# eprom-player.net
KiCad netlist of a schematic drawn in EAGLE
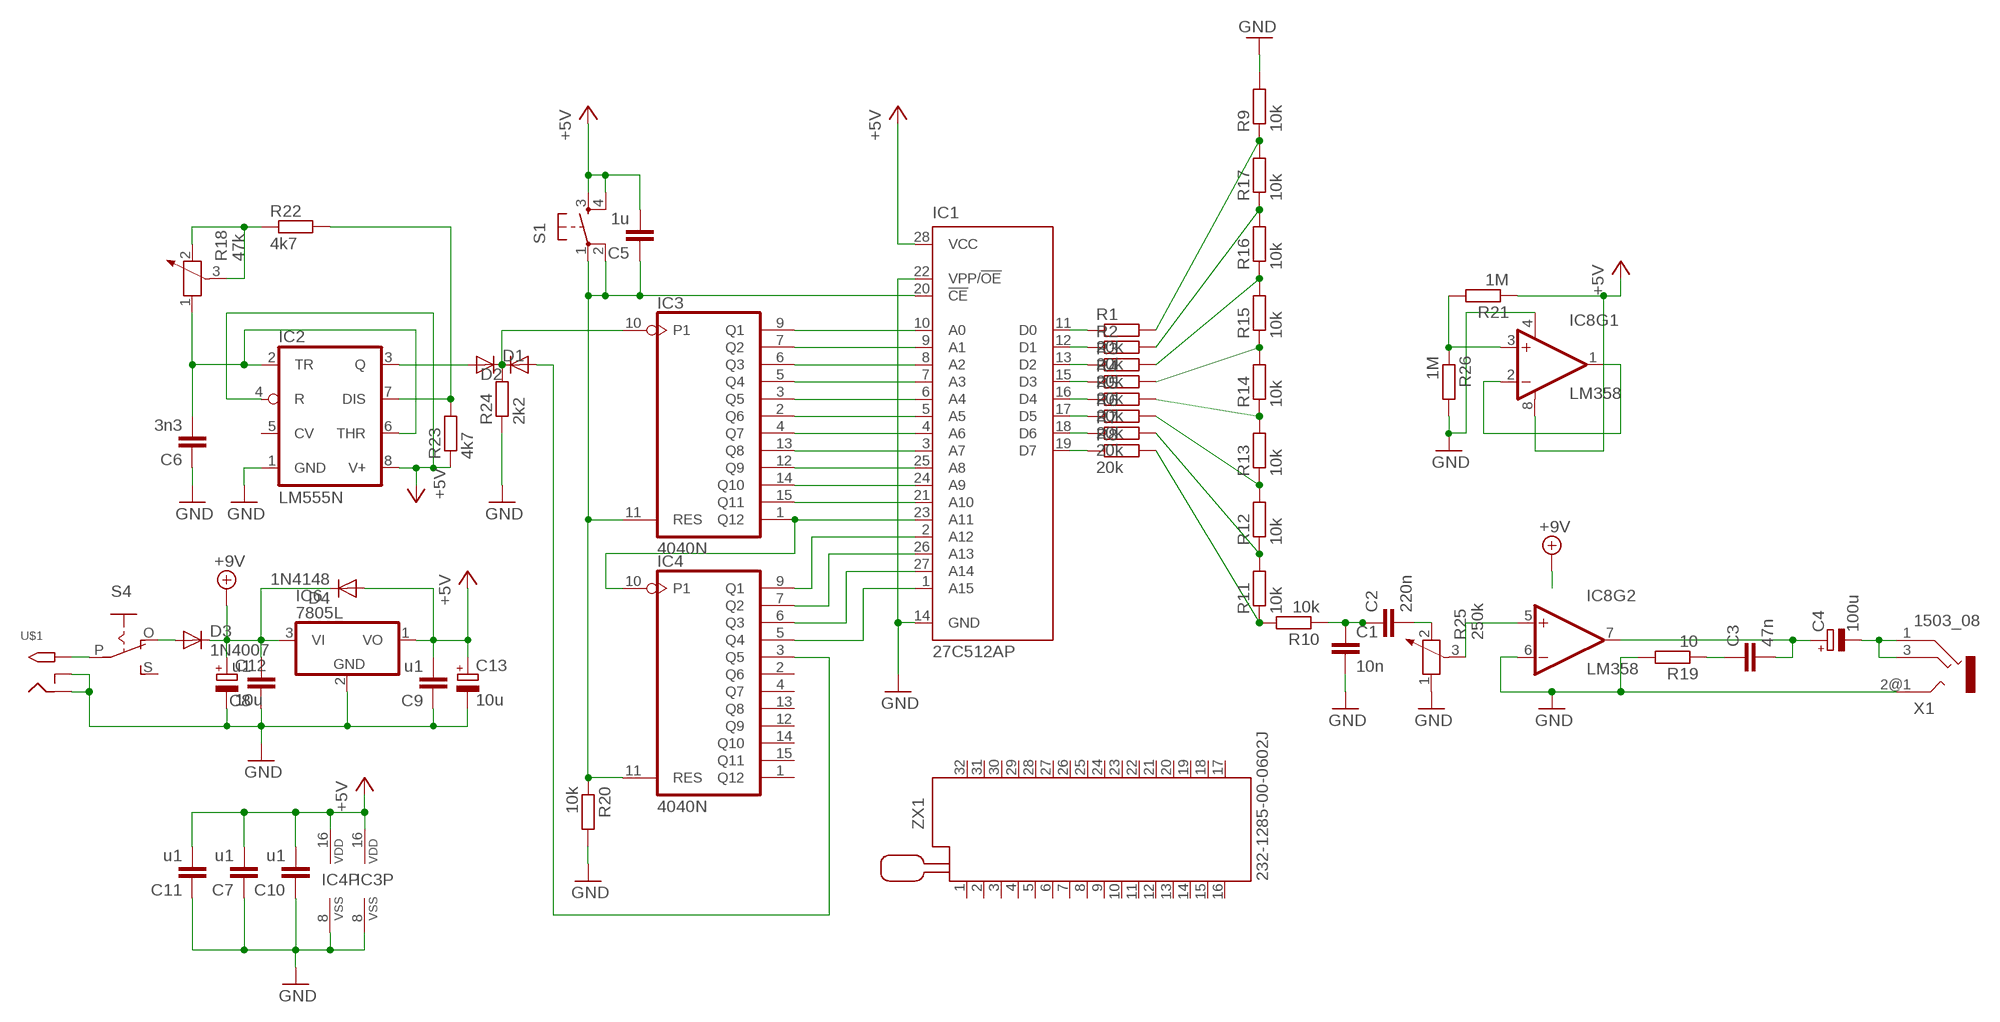
[diagram p0: schematic, sheet 1]

(export (version "E")
  (design (tool "Eeschema 10.0.6"))
  (components
    (comp (ref "C1")
      (value "10n")
      (footprint "eagle-import:C025-025X050")
      (libsource (lib "eagle-import") (part "C-EU025-025X050"))
    )
    (comp (ref "C2")
      (value "220n")
      (footprint "eagle-import:C025-025X050")
      (libsource (lib "eagle-import") (part "C-EU025-025X050"))
    )
    (comp (ref "C3")
      (value "47n")
      (footprint "eagle-import:C025-025X050")
      (libsource (lib "eagle-import") (part "C-EU025-025X050"))
    )
    (comp (ref "C4")
      (value "100u")
      (footprint "eagle-import:E2,5-5")
      (libsource (lib "eagle-import") (part "CPOL-EUE2.5-5"))
    )
    (comp (ref "C5")
      (value "1u")
      (footprint "eagle-import:C025-025X050")
      (libsource (lib "eagle-import") (part "C-EU025-025X050"))
    )
    (comp (ref "C6")
      (value "3n3")
      (footprint "eagle-import:C025-025X050")
      (libsource (lib "eagle-import") (part "C-EU025-025X050"))
    )
    (comp (ref "C7")
      (value "u1")
      (footprint "eagle-import:C025-025X050")
      (libsource (lib "eagle-import") (part "C-EU025-025X050"))
    )
    (comp (ref "C8")
      (value "u1")
      (footprint "eagle-import:C025-025X050")
      (libsource (lib "eagle-import") (part "C-EU025-025X050"))
    )
    (comp (ref "C9")
      (value "u1")
      (footprint "eagle-import:C025-025X050")
      (libsource (lib "eagle-import") (part "C-EU025-025X050"))
    )
    (comp (ref "C10")
      (value "u1")
      (footprint "eagle-import:C025-025X050")
      (libsource (lib "eagle-import") (part "C-EU025-025X050"))
    )
    (comp (ref "C11")
      (value "u1")
      (footprint "eagle-import:C025-025X050")
      (libsource (lib "eagle-import") (part "C-EU025-025X050"))
    )
    (comp (ref "C12")
      (value "10u")
      (footprint "eagle-import:E2,5-6")
      (libsource (lib "eagle-import") (part "CPOL-EUE2.5-6"))
    )
    (comp (ref "C13")
      (value "10u")
      (footprint "eagle-import:E2,5-6")
      (libsource (lib "eagle-import") (part "CPOL-EUE2.5-6"))
    )
    (comp (ref "D1")
      (value "DIODE-D-7.5")
      (footprint "eagle-import:D-7.5")
      (libsource (lib "eagle-import") (part "DIODE-D-7.5"))
    )
    (comp (ref "D2")
      (value "DIODE-D-7.5")
      (footprint "eagle-import:D-7.5")
      (libsource (lib "eagle-import") (part "DIODE-D-7.5"))
    )
    (comp (ref "D3")
      (value "1N4007")
      (footprint "eagle-import:D-2.5")
      (libsource (lib "eagle-import") (part "DIODE-D-2.5"))
    )
    (comp (ref "D4")
      (value "1N4148")
      (footprint "eagle-import:D-2.5")
      (libsource (lib "eagle-import") (part "DIODE-D-2.5"))
    )
    (comp (ref "IC1")
      (value "27C512AP")
      (footprint "eagle-import:DIL28-6")
      (fields (field (name "MPN") "M27C512-90B6"))
      (libsource (lib "eagle-import") (part "27512APC"))
    )
    (comp (ref "IC2")
      (value "LM555N")
      (footprint "eagle-import:DIL08-ROUND")
      (libsource (lib "eagle-import") (part "555NLM"))
    )
    (comp (ref "IC3")
      (value "4040N")
      (footprint "eagle-import:DIL16")
      (libsource (lib "eagle-import") (part "4040N"))
    )
    (comp (ref "IC4")
      (value "4040N")
      (footprint "eagle-import:DIL16")
      (libsource (lib "eagle-import") (part "4040N"))
    )
    (comp (ref "IC6")
      (value "7805L")
      (footprint "eagle-import:TO92")
      (libsource (lib "eagle-import") (part "78L05"))
    )
    (comp (ref "IC8")
      (value "LM358")
      (footprint "eagle-import:DIP08")
      (fields (field (name "PROD_ID") "IC-09172"))
      (libsource (lib "eagle-import") (part "LM358"))
    )
    (comp (ref "R1")
      (value "20k")
      (footprint "eagle-import:0204_7")
      (libsource (lib "eagle-import") (part "R-EU_0204/7"))
    )
    (comp (ref "R2")
      (value "20k")
      (footprint "eagle-import:0204_7")
      (libsource (lib "eagle-import") (part "R-EU_0204/7"))
    )
    (comp (ref "R3")
      (value "20k")
      (footprint "eagle-import:0204_7")
      (libsource (lib "eagle-import") (part "R-EU_0204/7"))
    )
    (comp (ref "R4")
      (value "20k")
      (footprint "eagle-import:0204V")
      (libsource (lib "eagle-import") (part "R-EU_0204/2V"))
    )
    (comp (ref "R5")
      (value "20k")
      (footprint "eagle-import:0204V")
      (libsource (lib "eagle-import") (part "R-EU_0204/2V"))
    )
    (comp (ref "R6")
      (value "20k")
      (footprint "eagle-import:0204V")
      (libsource (lib "eagle-import") (part "R-EU_0204/2V"))
    )
    (comp (ref "R7")
      (value "20k")
      (footprint "eagle-import:0204V")
      (libsource (lib "eagle-import") (part "R-EU_0204/2V"))
    )
    (comp (ref "R8")
      (value "20k")
      (footprint "eagle-import:0204V")
      (libsource (lib "eagle-import") (part "R-EU_0204/2V"))
    )
    (comp (ref "R9")
      (value "10k")
      (footprint "eagle-import:0204V")
      (libsource (lib "eagle-import") (part "R-EU_0204/2V"))
    )
    (comp (ref "R10")
      (value "10k")
      (footprint "eagle-import:0204V")
      (libsource (lib "eagle-import") (part "R-EU_0204/2V"))
    )
    (comp (ref "R11")
      (value "10k")
      (footprint "eagle-import:0204V")
      (libsource (lib "eagle-import") (part "R-EU_0204/2V"))
    )
    (comp (ref "R12")
      (value "10k")
      (footprint "eagle-import:0204V")
      (libsource (lib "eagle-import") (part "R-EU_0204/2V"))
    )
    (comp (ref "R13")
      (value "10k")
      (footprint "eagle-import:0204V")
      (libsource (lib "eagle-import") (part "R-EU_0204/2V"))
    )
    (comp (ref "R14")
      (value "10k")
      (footprint "eagle-import:0204V")
      (libsource (lib "eagle-import") (part "R-EU_0204/2V"))
    )
    (comp (ref "R15")
      (value "10k")
      (footprint "eagle-import:0204V")
      (libsource (lib "eagle-import") (part "R-EU_0204/2V"))
    )
    (comp (ref "R16")
      (value "10k")
      (footprint "eagle-import:0204V")
      (libsource (lib "eagle-import") (part "R-EU_0204/2V"))
    )
    (comp (ref "R17")
      (value "10k")
      (footprint "eagle-import:0204V")
      (libsource (lib "eagle-import") (part "R-EU_0204/2V"))
    )
    (comp (ref "R18")
      (value "47k")
      (footprint "eagle-import:PT-10")
      (libsource (lib "eagle-import") (part "POTENTIOMETER_PT-10"))
    )
    (comp (ref "R19")
      (value "10")
      (footprint "eagle-import:0204_5")
      (libsource (lib "eagle-import") (part "R-EU_0204/5"))
    )
    (comp (ref "R20")
      (value "10k")
      (footprint "eagle-import:0204V")
      (libsource (lib "eagle-import") (part "R-EU_0204/2V"))
    )
    (comp (ref "R21")
      (value "1M")
      (footprint "eagle-import:0204V")
      (libsource (lib "eagle-import") (part "R-EU_0204/2V"))
    )
    (comp (ref "R22")
      (value "4k7")
      (footprint "eagle-import:0204V")
      (libsource (lib "eagle-import") (part "R-EU_0204/2V"))
    )
    (comp (ref "R23")
      (value "4k7")
      (footprint "eagle-import:0204V")
      (libsource (lib "eagle-import") (part "R-EU_0204/2V"))
    )
    (comp (ref "R24")
      (value "2k2")
      (footprint "eagle-import:0204V")
      (libsource (lib "eagle-import") (part "R-EU_0204/2V"))
    )
    (comp (ref "R25")
      (value "250k")
      (footprint "eagle-import:PT-10")
      (libsource (lib "eagle-import") (part "POTENTIOMETER_PT-10"))
    )
    (comp (ref "R26")
      (value "1M")
      (footprint "eagle-import:0204V")
      (libsource (lib "eagle-import") (part "R-EU_0204/2V"))
    )
    (comp (ref "S1")
      (value "TAC_SWITCHPTH")
      (footprint "eagle-import:TACTILE-PTH")
      (libsource (lib "eagle-import") (part "TAC_SWITCHPTH"))
    )
    (comp (ref "S4")
      (value "EG1218S")
      (footprint "eagle-import:EG1218")
      (libsource (lib "eagle-import") (part "EG1218S"))
    )
    (comp (ref "U$1")
      (value "2.1MMJACKTHM")
      (footprint "eagle-import:PJ-102A")
      (libsource (lib "eagle-import") (part "2.1MMJACKTHM"))
    )
    (comp (ref "X1")
      (value "1503_08")
      (footprint "eagle-import:1503_08")
      (libsource (lib "eagle-import") (part "1503_?08"))
    )
    (comp (ref "ZX1")
      (value "232-1285-00-0602J")
      (footprint "eagle-import:232-1285-00-0602J")
      (fields (field (name "MF") "3M"))
      (libsource (lib "eagle-import") (part "232-?1285-00-0602J"))
    )
  )
  (nets
    (net (code "1") (name "+5V") (class "Default")
      (node (ref "C10") (pin "2") (pinfunction "2_2") (pintype "passive"))
      (node (ref "C11") (pin "2") (pinfunction "2_2") (pintype "passive"))
      (node (ref "C13") (pin "+") (pinfunction "+_+") (pintype "passive"))
      (node (ref "C5") (pin "2") (pinfunction "2_2") (pintype "passive"))
      (node (ref "C7") (pin "2") (pinfunction "2_2") (pintype "passive"))
      (node (ref "C9") (pin "2") (pinfunction "2_2") (pintype "passive"))
      (node (ref "D4") (pin "A") (pinfunction "A_A") (pintype "passive"))
      (node (ref "IC1") (pin "28") (pinfunction "VCC_28") (pintype "power_in"))
      (node (ref "IC2") (pin "4") (pinfunction "R_4") (pintype "input"))
      (node (ref "IC2") (pin "8") (pinfunction "V+_8") (pintype "power_in"))
      (node (ref "IC3") (pin "16") (pinfunction "VDD_16") (pintype "power_in"))
      (node (ref "IC4") (pin "16") (pinfunction "VDD_16") (pintype "power_in"))
      (node (ref "IC6") (pin "1") (pinfunction "VO_1") (pintype "passive"))
      (node (ref "IC8") (pin "8") (pinfunction "V+_8") (pintype "power_in"))
      (node (ref "R21") (pin "1") (pinfunction "1_1") (pintype "passive"))
      (node (ref "R23") (pin "1") (pinfunction "1_1") (pintype "passive"))
      (node (ref "S1") (pin "3") (pinfunction "3_3") (pintype "passive"))
      (node (ref "S1") (pin "4") (pinfunction "4_4") (pintype "passive"))
    )
    (net (code "2") (name "+9V") (class "Default")
      (node (ref "C12") (pin "+") (pinfunction "+_+") (pintype "passive"))
      (node (ref "C8") (pin "2") (pinfunction "2_2") (pintype "passive"))
      (node (ref "D3") (pin "C") (pinfunction "C_C") (pintype "passive"))
      (node (ref "D4") (pin "C") (pinfunction "C_C") (pintype "passive"))
      (node (ref "IC6") (pin "3") (pinfunction "VI_3") (pintype "input"))
    )
    (net (code "3") (name "GND") (class "Default")
      (node (ref "C1") (pin "2") (pinfunction "2_2") (pintype "passive"))
      (node (ref "C10") (pin "1") (pinfunction "1_1") (pintype "passive"))
      (node (ref "C11") (pin "1") (pinfunction "1_1") (pintype "passive"))
      (node (ref "C12") (pin "-") (pinfunction "-_-") (pintype "passive"))
      (node (ref "C13") (pin "-") (pinfunction "-_-") (pintype "passive"))
      (node (ref "C6") (pin "1") (pinfunction "1_1") (pintype "passive"))
      (node (ref "C7") (pin "1") (pinfunction "1_1") (pintype "passive"))
      (node (ref "C8") (pin "1") (pinfunction "1_1") (pintype "passive"))
      (node (ref "C9") (pin "1") (pinfunction "1_1") (pintype "passive"))
      (node (ref "IC1") (pin "14") (pinfunction "GND_14") (pintype "power_in"))
      (node (ref "IC1") (pin "22") (pinfunction "VPP/~{OE}_22") (pintype "input"))
      (node (ref "IC2") (pin "1") (pinfunction "GND_1") (pintype "power_in"))
      (node (ref "IC3") (pin "8") (pinfunction "VSS_8") (pintype "power_in"))
      (node (ref "IC4") (pin "8") (pinfunction "VSS_8") (pintype "power_in"))
      (node (ref "IC6") (pin "2") (pinfunction "GND_2") (pintype "passive"))
      (node (ref "IC8") (pin "4") (pinfunction "V-_4") (pintype "power_in"))
      (node (ref "IC8") (pin "6") (pinfunction "-IN_6") (pintype "input"))
      (node (ref "R19") (pin "2") (pinfunction "2_2") (pintype "passive"))
      (node (ref "R20") (pin "2") (pinfunction "2_2") (pintype "passive"))
      (node (ref "R24") (pin "1") (pinfunction "1_1") (pintype "passive"))
      (node (ref "R25") (pin "1") (pinfunction "1_1") (pintype "passive"))
      (node (ref "R26") (pin "2") (pinfunction "2_2") (pintype "passive"))
      (node (ref "R9") (pin "2") (pinfunction "2_2") (pintype "passive"))
      (node (ref "U$1") (pin "RING") (pinfunction "RING_RING") (pintype "bidirectional"))
      (node (ref "U$1") (pin "RING_SW") (pinfunction "RING_SW_RING_SW") (pintype "bidirectional"))
      (node (ref "X1") (pin "2@1") (pinfunction "2_2@1") (pintype "passive"))
    )
    (net (code "4") (name "Net-(C1-Pad1)") (class "Default")
      (node (ref "C1") (pin "1") (pinfunction "1_1") (pintype "passive"))
      (node (ref "C2") (pin "1") (pinfunction "1_1") (pintype "passive"))
      (node (ref "R10") (pin "1") (pinfunction "1_1") (pintype "passive"))
    )
    (net (code "5") (name "Net-(C2-Pad2)") (class "Default")
      (node (ref "C2") (pin "2") (pinfunction "2_2") (pintype "passive"))
      (node (ref "R25") (pin "2") (pinfunction "2_2") (pintype "passive"))
    )
    (net (code "6") (name "Net-(C3-Pad1)") (class "Default")
      (node (ref "C3") (pin "1") (pinfunction "1_1") (pintype "passive"))
      (node (ref "R19") (pin "1") (pinfunction "1_1") (pintype "passive"))
    )
    (net (code "7") (name "Net-(C4-Pad-)") (class "Default")
      (node (ref "C4") (pin "-") (pinfunction "-_-") (pintype "passive"))
      (node (ref "X1") (pin "1") (pinfunction "1_1") (pintype "passive"))
      (node (ref "X1") (pin "3") (pinfunction "3_3") (pintype "passive"))
    )
    (net (code "8") (name "Net-(D3-PadA)") (class "Default")
      (node (ref "D3") (pin "A") (pinfunction "A_A") (pintype "passive"))
      (node (ref "S4") (pin "O") (pinfunction "O_O") (pintype "passive"))
    )
    (net (code "9") (name "Net-(IC1-A0)") (class "Default")
      (node (ref "IC1") (pin "10") (pinfunction "A0_10") (pintype "input"))
      (node (ref "IC3") (pin "9") (pinfunction "Q1_9") (pintype "output"))
    )
    (net (code "10") (name "Net-(IC1-A1)") (class "Default")
      (node (ref "IC1") (pin "9") (pinfunction "A1_9") (pintype "input"))
      (node (ref "IC3") (pin "7") (pinfunction "Q2_7") (pintype "output"))
    )
    (net (code "11") (name "Net-(IC1-A2)") (class "Default")
      (node (ref "IC1") (pin "8") (pinfunction "A2_8") (pintype "input"))
      (node (ref "IC3") (pin "6") (pinfunction "Q3_6") (pintype "output"))
    )
    (net (code "12") (name "Net-(IC1-A3)") (class "Default")
      (node (ref "IC1") (pin "7") (pinfunction "A3_7") (pintype "input"))
      (node (ref "IC3") (pin "5") (pinfunction "Q4_5") (pintype "output"))
    )
    (net (code "13") (name "Net-(IC1-A4)") (class "Default")
      (node (ref "IC1") (pin "6") (pinfunction "A4_6") (pintype "input"))
      (node (ref "IC3") (pin "3") (pinfunction "Q5_3") (pintype "output"))
    )
    (net (code "14") (name "Net-(IC1-A5)") (class "Default")
      (node (ref "IC1") (pin "5") (pinfunction "A5_5") (pintype "input"))
      (node (ref "IC3") (pin "2") (pinfunction "Q6_2") (pintype "output"))
    )
    (net (code "15") (name "Net-(IC1-A6)") (class "Default")
      (node (ref "IC1") (pin "4") (pinfunction "A6_4") (pintype "input"))
      (node (ref "IC3") (pin "4") (pinfunction "Q7_4") (pintype "output"))
    )
    (net (code "16") (name "Net-(IC1-A7)") (class "Default")
      (node (ref "IC1") (pin "3") (pinfunction "A7_3") (pintype "input"))
      (node (ref "IC3") (pin "13") (pinfunction "Q8_13") (pintype "output"))
    )
    (net (code "17") (name "Net-(IC1-A8)") (class "Default")
      (node (ref "IC1") (pin "25") (pinfunction "A8_25") (pintype "input"))
      (node (ref "IC3") (pin "12") (pinfunction "Q9_12") (pintype "output"))
    )
    (net (code "18") (name "Net-(IC1-A9)") (class "Default")
      (node (ref "IC1") (pin "24") (pinfunction "A9_24") (pintype "input"))
      (node (ref "IC3") (pin "14") (pinfunction "Q10_14") (pintype "output"))
    )
    (net (code "19") (name "Net-(IC1-A10)") (class "Default")
      (node (ref "IC1") (pin "21") (pinfunction "A10_21") (pintype "input"))
      (node (ref "IC3") (pin "15") (pinfunction "Q11_15") (pintype "output"))
    )
    (net (code "20") (name "Net-(IC1-A11)") (class "Default")
      (node (ref "IC1") (pin "23") (pinfunction "A11_23") (pintype "input"))
      (node (ref "IC3") (pin "1") (pinfunction "Q12_1") (pintype "output"))
      (node (ref "IC4") (pin "10") (pinfunction "P1_10") (pintype "input"))
    )
    (net (code "21") (name "Net-(IC1-A12)") (class "Default")
      (node (ref "IC1") (pin "2") (pinfunction "A12_2") (pintype "input"))
      (node (ref "IC4") (pin "9") (pinfunction "Q1_9") (pintype "output"))
    )
    (net (code "22") (name "Net-(IC1-A13)") (class "Default")
      (node (ref "IC1") (pin "26") (pinfunction "A13_26") (pintype "input"))
      (node (ref "IC4") (pin "7") (pinfunction "Q2_7") (pintype "output"))
    )
    (net (code "23") (name "Net-(IC1-A14)") (class "Default")
      (node (ref "IC1") (pin "27") (pinfunction "A14_27") (pintype "input"))
      (node (ref "IC4") (pin "6") (pinfunction "Q3_6") (pintype "output"))
    )
    (net (code "24") (name "Net-(IC1-A15)") (class "Default")
      (node (ref "IC1") (pin "1") (pinfunction "A15_1") (pintype "input"))
      (node (ref "IC4") (pin "5") (pinfunction "Q4_5") (pintype "output"))
    )
    (net (code "25") (name "Net-(IC1-D0)") (class "Default")
      (node (ref "IC1") (pin "11") (pinfunction "D0_11") (pintype "tri_state"))
      (node (ref "R1") (pin "1") (pinfunction "1_1") (pintype "passive"))
    )
    (net (code "26") (name "Net-(IC1-D1)") (class "Default")
      (node (ref "IC1") (pin "12") (pinfunction "D1_12") (pintype "tri_state"))
      (node (ref "R2") (pin "1") (pinfunction "1_1") (pintype "passive"))
    )
    (net (code "27") (name "Net-(IC1-D2)") (class "Default")
      (node (ref "IC1") (pin "13") (pinfunction "D2_13") (pintype "tri_state"))
      (node (ref "R3") (pin "1") (pinfunction "1_1") (pintype "passive"))
    )
    (net (code "28") (name "Net-(IC1-D3)") (class "Default")
      (node (ref "IC1") (pin "15") (pinfunction "D3_15") (pintype "tri_state"))
      (node (ref "R4") (pin "1") (pinfunction "1_1") (pintype "passive"))
    )
    (net (code "29") (name "Net-(IC1-D4)") (class "Default")
      (node (ref "IC1") (pin "16") (pinfunction "D4_16") (pintype "tri_state"))
      (node (ref "R5") (pin "1") (pinfunction "1_1") (pintype "passive"))
    )
    (net (code "30") (name "Net-(IC1-D5)") (class "Default")
      (node (ref "IC1") (pin "17") (pinfunction "D5_17") (pintype "tri_state"))
      (node (ref "R6") (pin "1") (pinfunction "1_1") (pintype "passive"))
    )
    (net (code "31") (name "Net-(IC1-D6)") (class "Default")
      (node (ref "IC1") (pin "18") (pinfunction "D6_18") (pintype "tri_state"))
      (node (ref "R7") (pin "1") (pinfunction "1_1") (pintype "passive"))
    )
    (net (code "32") (name "Net-(IC1-D7)") (class "Default")
      (node (ref "IC1") (pin "19") (pinfunction "D7_19") (pintype "tri_state"))
      (node (ref "R8") (pin "1") (pinfunction "1_1") (pintype "passive"))
    )
    (net (code "33") (name "Net-(IC1-~{CE})") (class "Default")
      (node (ref "C5") (pin "1") (pinfunction "1_1") (pintype "passive"))
      (node (ref "IC1") (pin "20") (pinfunction "~{CE}_20") (pintype "input"))
      (node (ref "IC3") (pin "11") (pinfunction "RES_11") (pintype "input"))
      (node (ref "IC4") (pin "11") (pinfunction "RES_11") (pintype "input"))
      (node (ref "R20") (pin "1") (pinfunction "1_1") (pintype "passive"))
      (node (ref "S1") (pin "1") (pinfunction "1_1") (pintype "passive"))
      (node (ref "S1") (pin "2") (pinfunction "2_2") (pintype "passive"))
    )
    (net (code "34") (name "Net-(IC2-DIS)") (class "Default")
      (node (ref "IC2") (pin "7") (pinfunction "DIS_7") (pintype "input"))
      (node (ref "R22") (pin "2") (pinfunction "2_2") (pintype "passive"))
      (node (ref "R23") (pin "2") (pinfunction "2_2") (pintype "passive"))
    )
    (net (code "35") (name "Net-(IC2-Q)") (class "Default")
      (node (ref "D1") (pin "A") (pinfunction "A_A") (pintype "passive"))
      (node (ref "IC2") (pin "3") (pinfunction "Q_3") (pintype "output"))
    )
    (net (code "36") (name "Net-(IC2-THR)") (class "Default")
      (node (ref "C6") (pin "2") (pinfunction "2_2") (pintype "passive"))
      (node (ref "IC2") (pin "2") (pinfunction "TR_2") (pintype "input"))
      (node (ref "IC2") (pin "6") (pinfunction "THR_6") (pintype "input"))
      (node (ref "R18") (pin "1") (pinfunction "1_1") (pintype "passive"))
    )
    (net (code "37") (name "Net-(IC3A-P1)") (class "Default")
      (node (ref "D1") (pin "C") (pinfunction "C_C") (pintype "passive"))
      (node (ref "D2") (pin "C") (pinfunction "C_C") (pintype "passive"))
      (node (ref "IC3") (pin "10") (pinfunction "P1_10") (pintype "input"))
      (node (ref "R24") (pin "2") (pinfunction "2_2") (pintype "passive"))
    )
    (net (code "38") (name "Net-(IC4A-Q5)") (class "Default")
      (node (ref "D2") (pin "A") (pinfunction "A_A") (pintype "passive"))
      (node (ref "IC4") (pin "3") (pinfunction "Q5_3") (pintype "output"))
    )
    (net (code "39") (name "Net-(IC8A-+IN)") (class "Default")
      (node (ref "IC8") (pin "3") (pinfunction "+IN_3") (pintype "input"))
      (node (ref "R21") (pin "2") (pinfunction "2_2") (pintype "passive"))
      (node (ref "R26") (pin "1") (pinfunction "1_1") (pintype "passive"))
    )
    (net (code "40") (name "Net-(IC8A--IN)") (class "Default")
      (node (ref "IC8") (pin "1") (pinfunction "OUT_1") (pintype "output"))
      (node (ref "IC8") (pin "2") (pinfunction "-IN_2") (pintype "input"))
    )
    (net (code "41") (name "Net-(IC8B-+IN)") (class "Default")
      (node (ref "IC8") (pin "5") (pinfunction "+IN_5") (pintype "input"))
      (node (ref "R25") (pin "3") (pinfunction "3_3") (pintype "passive"))
    )
    (net (code "42") (name "Net-(IC8B-OUT)") (class "Default")
      (node (ref "C3") (pin "2") (pinfunction "2_2") (pintype "passive"))
      (node (ref "C4") (pin "+") (pinfunction "+_+") (pintype "passive"))
      (node (ref "IC8") (pin "7") (pinfunction "OUT_7") (pintype "output"))
    )
    (net (code "43") (name "Net-(R1-Pad2)") (class "Default")
      (node (ref "R1") (pin "2") (pinfunction "2_2") (pintype "passive"))
      (node (ref "R17") (pin "2") (pinfunction "2_2") (pintype "passive"))
      (node (ref "R9") (pin "1") (pinfunction "1_1") (pintype "passive"))
    )
    (net (code "44") (name "Net-(R10-Pad2)") (class "Default")
      (node (ref "R10") (pin "2") (pinfunction "2_2") (pintype "passive"))
      (node (ref "R11") (pin "1") (pinfunction "1_1") (pintype "passive"))
      (node (ref "R8") (pin "2") (pinfunction "2_2") (pintype "passive"))
    )
    (net (code "45") (name "Net-(R11-Pad2)") (class "Default")
      (node (ref "R11") (pin "2") (pinfunction "2_2") (pintype "passive"))
      (node (ref "R12") (pin "1") (pinfunction "1_1") (pintype "passive"))
      (node (ref "R7") (pin "2") (pinfunction "2_2") (pintype "passive"))
    )
    (net (code "46") (name "Net-(R12-Pad2)") (class "Default")
      (node (ref "R12") (pin "2") (pinfunction "2_2") (pintype "passive"))
      (node (ref "R13") (pin "1") (pinfunction "1_1") (pintype "passive"))
      (node (ref "R6") (pin "2") (pinfunction "2_2") (pintype "passive"))
    )
    (net (code "47") (name "Net-(R13-Pad2)") (class "Default")
      (node (ref "R13") (pin "2") (pinfunction "2_2") (pintype "passive"))
      (node (ref "R14") (pin "1") (pinfunction "1_1") (pintype "passive"))
      (node (ref "R5") (pin "2") (pinfunction "2_2") (pintype "passive"))
    )
    (net (code "48") (name "Net-(R14-Pad2)") (class "Default")
      (node (ref "R14") (pin "2") (pinfunction "2_2") (pintype "passive"))
      (node (ref "R15") (pin "1") (pinfunction "1_1") (pintype "passive"))
      (node (ref "R4") (pin "2") (pinfunction "2_2") (pintype "passive"))
    )
    (net (code "49") (name "Net-(R15-Pad2)") (class "Default")
      (node (ref "R15") (pin "2") (pinfunction "2_2") (pintype "passive"))
      (node (ref "R16") (pin "1") (pinfunction "1_1") (pintype "passive"))
      (node (ref "R3") (pin "2") (pinfunction "2_2") (pintype "passive"))
    )
    (net (code "50") (name "Net-(R16-Pad2)") (class "Default")
      (node (ref "R16") (pin "2") (pinfunction "2_2") (pintype "passive"))
      (node (ref "R17") (pin "1") (pinfunction "1_1") (pintype "passive"))
      (node (ref "R2") (pin "2") (pinfunction "2_2") (pintype "passive"))
    )
    (net (code "51") (name "Net-(R18-Pad2)") (class "Default")
      (node (ref "R18") (pin "2") (pinfunction "2_2") (pintype "passive"))
      (node (ref "R18") (pin "3") (pinfunction "3_3") (pintype "passive"))
      (node (ref "R22") (pin "1") (pinfunction "1_1") (pintype "passive"))
    )
    (net (code "52") (name "Net-(S4-PadP)") (class "Default")
      (node (ref "S4") (pin "P") (pinfunction "P_P") (pintype "passive"))
      (node (ref "U$1") (pin "TIP") (pinfunction "TIP_TIP") (pintype "bidirectional"))
    )
    (net (code "53") (name "unconnected-(IC2-CV-Pad5)") (class "Default")
      (node (ref "IC2") (pin "5") (pinfunction "CV_5") (pintype "input"))
    )
    (net (code "54") (name "unconnected-(IC4A-Q6-Pad2)") (class "Default")
      (node (ref "IC4") (pin "2") (pinfunction "Q6_2") (pintype "output"))
    )
    (net (code "55") (name "unconnected-(IC4A-Q7-Pad4)") (class "Default")
      (node (ref "IC4") (pin "4") (pinfunction "Q7_4") (pintype "output"))
    )
    (net (code "56") (name "unconnected-(IC4A-Q8-Pad13)") (class "Default")
      (node (ref "IC4") (pin "13") (pinfunction "Q8_13") (pintype "output"))
    )
    (net (code "57") (name "unconnected-(IC4A-Q9-Pad12)") (class "Default")
      (node (ref "IC4") (pin "12") (pinfunction "Q9_12") (pintype "output"))
    )
    (net (code "58") (name "unconnected-(IC4A-Q10-Pad14)") (class "Default")
      (node (ref "IC4") (pin "14") (pinfunction "Q10_14") (pintype "output"))
    )
    (net (code "59") (name "unconnected-(IC4A-Q11-Pad15)") (class "Default")
      (node (ref "IC4") (pin "15") (pinfunction "Q11_15") (pintype "output"))
    )
    (net (code "60") (name "unconnected-(IC4A-Q12-Pad1)") (class "Default")
      (node (ref "IC4") (pin "1") (pinfunction "Q12_1") (pintype "output"))
    )
    (net (code "61") (name "unconnected-(S4-PadS)") (class "Default")
      (node (ref "S4") (pin "S") (pinfunction "S_S") (pintype "passive"))
    )
    (net (code "62") (name "unconnected-(X1-2-Pad2@2)") (class "Default")
      (node (ref "X1") (pin "2@2") (pinfunction "2_2@2") (pintype "passive"))
    )
    (net (code "63") (name "unconnected-(ZX1-Pad1)") (class "Default")
      (node (ref "ZX1") (pin "1") (pinfunction "1_1") (pintype "passive"))
    )
    (net (code "64") (name "unconnected-(ZX1-Pad2)") (class "Default")
      (node (ref "ZX1") (pin "2") (pinfunction "2_2") (pintype "passive"))
    )
    (net (code "65") (name "unconnected-(ZX1-Pad3)") (class "Default")
      (node (ref "ZX1") (pin "3") (pinfunction "3_3") (pintype "passive"))
    )
    (net (code "66") (name "unconnected-(ZX1-Pad4)") (class "Default")
      (node (ref "ZX1") (pin "4") (pinfunction "4_4") (pintype "passive"))
    )
    (net (code "67") (name "unconnected-(ZX1-Pad5)") (class "Default")
      (node (ref "ZX1") (pin "5") (pinfunction "5_5") (pintype "passive"))
    )
    (net (code "68") (name "unconnected-(ZX1-Pad6)") (class "Default")
      (node (ref "ZX1") (pin "6") (pinfunction "6_6") (pintype "passive"))
    )
    (net (code "69") (name "unconnected-(ZX1-Pad7)") (class "Default")
      (node (ref "ZX1") (pin "7") (pinfunction "7_7") (pintype "passive"))
    )
    (net (code "70") (name "unconnected-(ZX1-Pad8)") (class "Default")
      (node (ref "ZX1") (pin "8") (pinfunction "8_8") (pintype "passive"))
    )
    (net (code "71") (name "unconnected-(ZX1-Pad9)") (class "Default")
      (node (ref "ZX1") (pin "9") (pinfunction "9_9") (pintype "passive"))
    )
    (net (code "72") (name "unconnected-(ZX1-Pad10)") (class "Default")
      (node (ref "ZX1") (pin "10") (pinfunction "10_10") (pintype "passive"))
    )
    (net (code "73") (name "unconnected-(ZX1-Pad11)") (class "Default")
      (node (ref "ZX1") (pin "11") (pinfunction "11_11") (pintype "passive"))
    )
    (net (code "74") (name "unconnected-(ZX1-Pad12)") (class "Default")
      (node (ref "ZX1") (pin "12") (pinfunction "12_12") (pintype "passive"))
    )
    (net (code "75") (name "unconnected-(ZX1-Pad13)") (class "Default")
      (node (ref "ZX1") (pin "13") (pinfunction "13_13") (pintype "passive"))
    )
    (net (code "76") (name "unconnected-(ZX1-Pad14)") (class "Default")
      (node (ref "ZX1") (pin "14") (pinfunction "14_14") (pintype "passive"))
    )
    (net (code "77") (name "unconnected-(ZX1-Pad15)") (class "Default")
      (node (ref "ZX1") (pin "15") (pinfunction "15_15") (pintype "passive"))
    )
    (net (code "78") (name "unconnected-(ZX1-Pad16)") (class "Default")
      (node (ref "ZX1") (pin "16") (pinfunction "16_16") (pintype "passive"))
    )
    (net (code "79") (name "unconnected-(ZX1-Pad17)") (class "Default")
      (node (ref "ZX1") (pin "17") (pinfunction "17_17") (pintype "passive"))
    )
    (net (code "80") (name "unconnected-(ZX1-Pad18)") (class "Default")
      (node (ref "ZX1") (pin "18") (pinfunction "18_18") (pintype "passive"))
    )
    (net (code "81") (name "unconnected-(ZX1-Pad19)") (class "Default")
      (node (ref "ZX1") (pin "19") (pinfunction "19_19") (pintype "passive"))
    )
    (net (code "82") (name "unconnected-(ZX1-Pad20)") (class "Default")
      (node (ref "ZX1") (pin "20") (pinfunction "20_20") (pintype "passive"))
    )
    (net (code "83") (name "unconnected-(ZX1-Pad21)") (class "Default")
      (node (ref "ZX1") (pin "21") (pinfunction "21_21") (pintype "passive"))
    )
    (net (code "84") (name "unconnected-(ZX1-Pad22)") (class "Default")
      (node (ref "ZX1") (pin "22") (pinfunction "22_22") (pintype "passive"))
    )
    (net (code "85") (name "unconnected-(ZX1-Pad23)") (class "Default")
      (node (ref "ZX1") (pin "23") (pinfunction "23_23") (pintype "passive"))
    )
    (net (code "86") (name "unconnected-(ZX1-Pad24)") (class "Default")
      (node (ref "ZX1") (pin "24") (pinfunction "24_24") (pintype "passive"))
    )
    (net (code "87") (name "unconnected-(ZX1-Pad25)") (class "Default")
      (node (ref "ZX1") (pin "25") (pinfunction "25_25") (pintype "passive"))
    )
    (net (code "88") (name "unconnected-(ZX1-Pad26)") (class "Default")
      (node (ref "ZX1") (pin "26") (pinfunction "26_26") (pintype "passive"))
    )
    (net (code "89") (name "unconnected-(ZX1-Pad27)") (class "Default")
      (node (ref "ZX1") (pin "27") (pinfunction "27_27") (pintype "passive"))
    )
    (net (code "90") (name "unconnected-(ZX1-Pad28)") (class "Default")
      (node (ref "ZX1") (pin "28") (pinfunction "28_28") (pintype "passive"))
    )
    (net (code "91") (name "unconnected-(ZX1-Pad29)") (class "Default")
      (node (ref "ZX1") (pin "29") (pinfunction "29_29") (pintype "passive"))
    )
    (net (code "92") (name "unconnected-(ZX1-Pad30)") (class "Default")
      (node (ref "ZX1") (pin "30") (pinfunction "30_30") (pintype "passive"))
    )
    (net (code "93") (name "unconnected-(ZX1-Pad31)") (class "Default")
      (node (ref "ZX1") (pin "31") (pinfunction "31_31") (pintype "passive"))
    )
    (net (code "94") (name "unconnected-(ZX1-Pad32)") (class "Default")
      (node (ref "ZX1") (pin "32") (pinfunction "32_32") (pintype "passive"))
    )
  )
)
